# mic-preamp.net
KiCad netlist of a schematic drawn in EAGLE
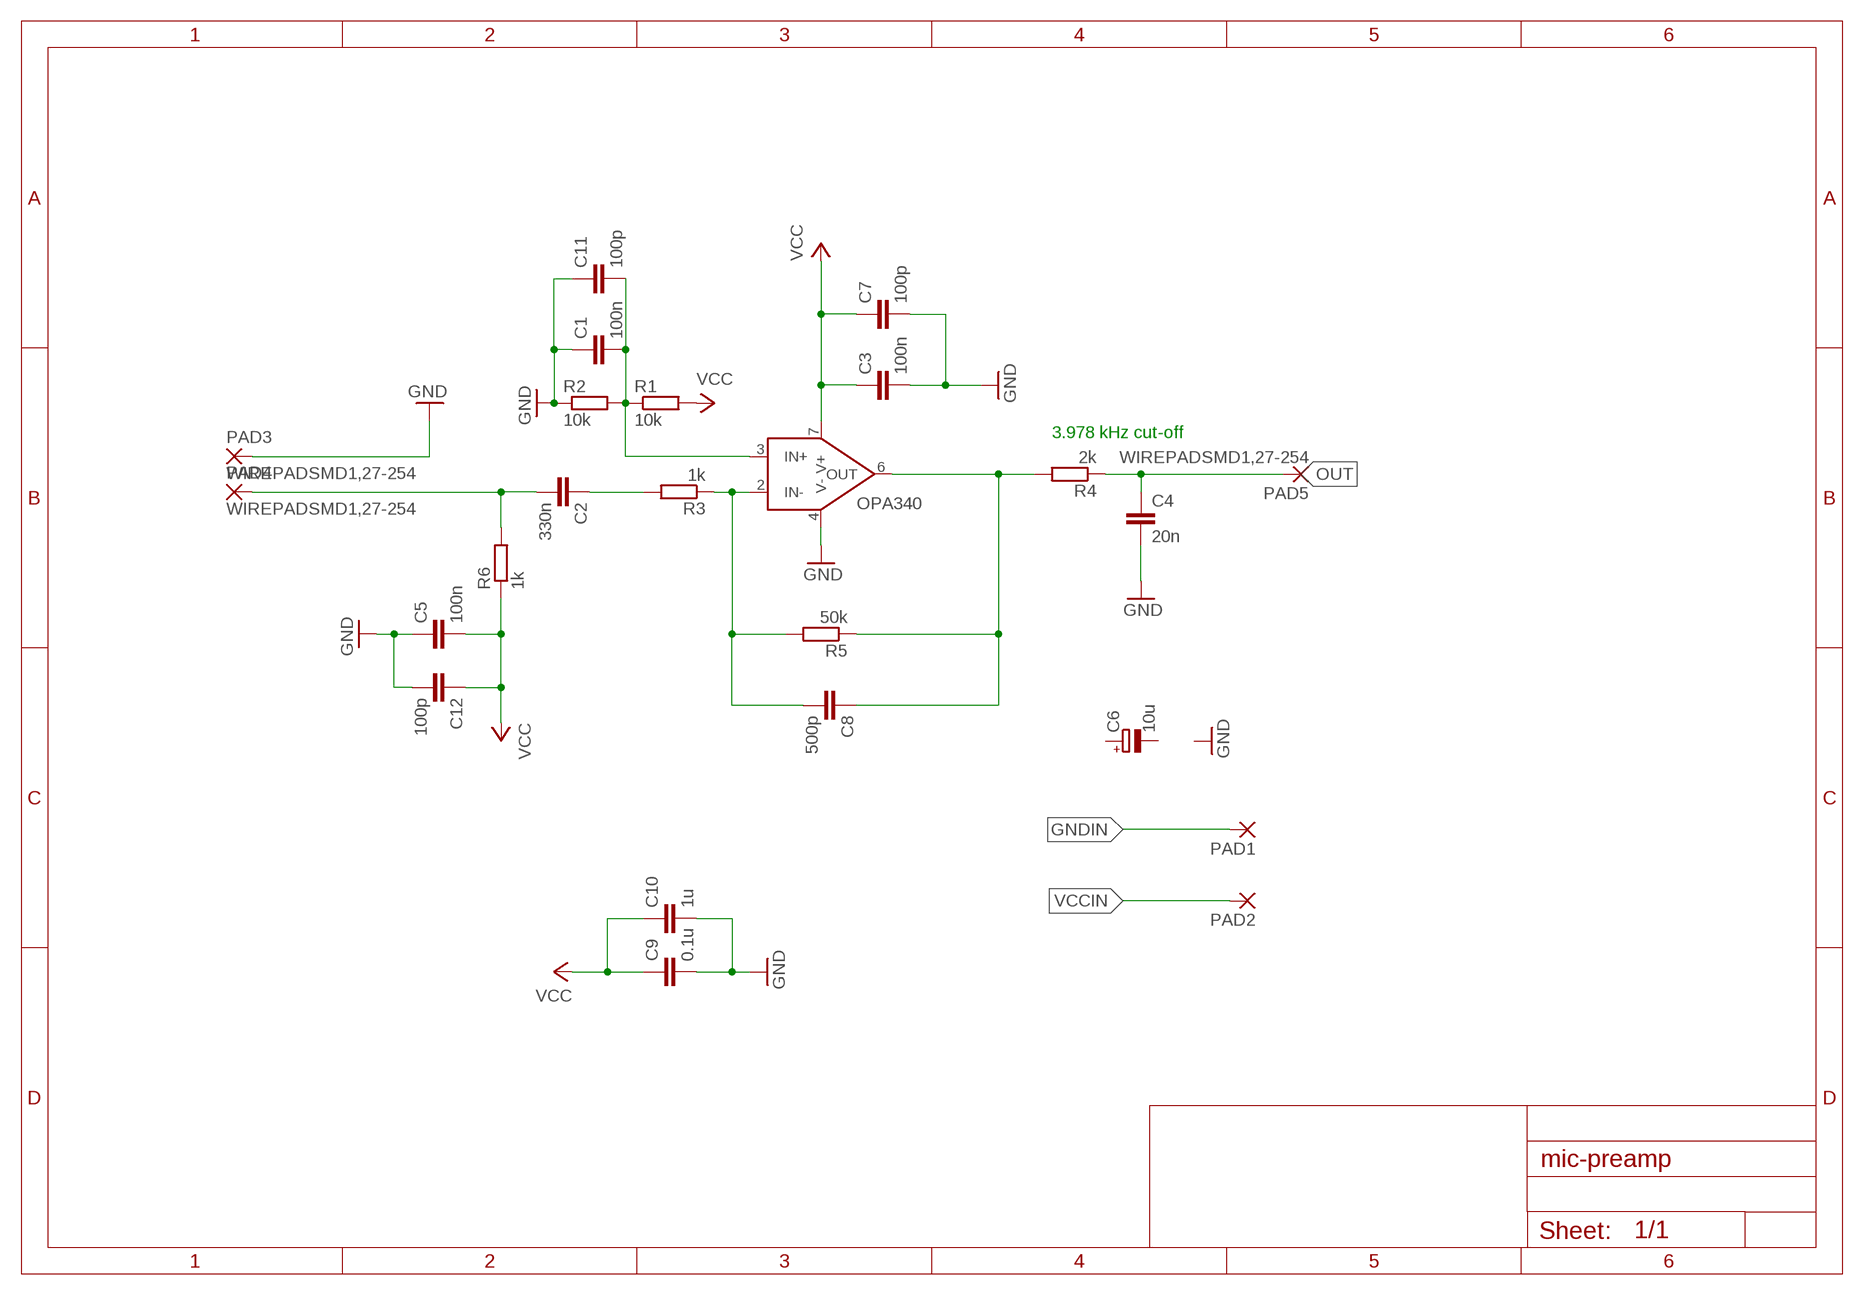
[diagram p0: schematic, sheet 1]

(export (version "E")
  (design (tool "Eeschema 10.0.6"))
  (components
    (comp (ref "C1")
      (value "100n")
      (footprint "eagle-import:C0805")
      (libsource (lib "eagle-import") (part "C-EUC0805"))
    )
    (comp (ref "C2")
      (value "330n")
      (footprint "eagle-import:C0805")
      (libsource (lib "eagle-import") (part "C-EUC0805"))
    )
    (comp (ref "C3")
      (value "100n")
      (footprint "eagle-import:C0805")
      (libsource (lib "eagle-import") (part "C-EUC0805"))
    )
    (comp (ref "C4")
      (value "20n")
      (footprint "eagle-import:C0805")
      (libsource (lib "eagle-import") (part "C-EUC0805"))
    )
    (comp (ref "C5")
      (value "100n")
      (footprint "eagle-import:C0805")
      (libsource (lib "eagle-import") (part "C-EUC0805"))
    )
    (comp (ref "C6")
      (value "10u")
      (footprint "eagle-import:E2,5-6E")
      (libsource (lib "eagle-import") (part "CPOL-EUE2,5-6E"))
    )
    (comp (ref "C7")
      (value "100p")
      (footprint "eagle-import:C0805")
      (libsource (lib "eagle-import") (part "C-EUC0805"))
    )
    (comp (ref "C8")
      (value "500p")
      (footprint "eagle-import:C0805")
      (libsource (lib "eagle-import") (part "C-EUC0805"))
    )
    (comp (ref "C9")
      (value "0.1u")
      (footprint "eagle-import:C0805")
      (libsource (lib "eagle-import") (part "C-EUC0805"))
    )
    (comp (ref "C10")
      (value "1u")
      (footprint "eagle-import:C0805")
      (libsource (lib "eagle-import") (part "C-EUC0805"))
    )
    (comp (ref "C11")
      (value "100p")
      (footprint "eagle-import:C0805")
      (libsource (lib "eagle-import") (part "C-EUC0805"))
    )
    (comp (ref "C12")
      (value "100p")
      (footprint "eagle-import:C0805")
      (libsource (lib "eagle-import") (part "C-EUC0805"))
    )
    (comp (ref "OPA340")
      (value "OPA340")
      (footprint "eagle-import:DIL08")
      (libsource (lib "eagle-import") (part "OPA340"))
    )
    (comp (ref "PAD1")
      (value "WIREPADSMD2,54-5,08")
      (footprint "eagle-import:SMD2,54-5,08")
      (libsource (lib "eagle-import") (part "WIREPADSMD2,54-5,08"))
    )
    (comp (ref "PAD2")
      (value "WIREPADSMD2,54-5,08")
      (footprint "eagle-import:SMD2,54-5,08")
      (libsource (lib "eagle-import") (part "WIREPADSMD2,54-5,08"))
    )
    (comp (ref "PAD3")
      (value "WIREPADSMD1,27-254")
      (footprint "eagle-import:SMD1,27-2,54")
      (libsource (lib "eagle-import") (part "WIREPADSMD1,27-254"))
    )
    (comp (ref "PAD4")
      (value "WIREPADSMD1,27-254")
      (footprint "eagle-import:SMD1,27-2,54")
      (libsource (lib "eagle-import") (part "WIREPADSMD1,27-254"))
    )
    (comp (ref "PAD5")
      (value "WIREPADSMD1,27-254")
      (footprint "eagle-import:SMD1,27-2,54")
      (libsource (lib "eagle-import") (part "WIREPADSMD1,27-254"))
    )
    (comp (ref "R1")
      (value "10k")
      (footprint "eagle-import:R0805")
      (libsource (lib "eagle-import") (part "R-EU_R0805"))
    )
    (comp (ref "R2")
      (value "10k")
      (footprint "eagle-import:R0805")
      (libsource (lib "eagle-import") (part "R-EU_R0805"))
    )
    (comp (ref "R3")
      (value "1k")
      (footprint "eagle-import:R0805")
      (libsource (lib "eagle-import") (part "R-EU_R0805"))
    )
    (comp (ref "R4")
      (value "2k")
      (footprint "eagle-import:R0805")
      (libsource (lib "eagle-import") (part "R-EU_R0805"))
    )
    (comp (ref "R5")
      (value "50k")
      (footprint "eagle-import:R0805")
      (libsource (lib "eagle-import") (part "R-EU_R0805"))
    )
    (comp (ref "R6")
      (value "1k")
      (footprint "eagle-import:R0805")
      (libsource (lib "eagle-import") (part "R-EU_R0805"))
    )
  )
  (nets
    (net (code "1") (name "GND") (class "Default")
      (node (ref "C1") (pin "1") (pinfunction "1_1") (pintype "passive"))
      (node (ref "C10") (pin "2") (pinfunction "2_2") (pintype "passive"))
      (node (ref "C11") (pin "1") (pinfunction "1_1") (pintype "passive"))
      (node (ref "C12") (pin "2") (pinfunction "2_2") (pintype "passive"))
      (node (ref "C3") (pin "2") (pinfunction "2_2") (pintype "passive"))
      (node (ref "C4") (pin "2") (pinfunction "2_2") (pintype "passive"))
      (node (ref "C5") (pin "1") (pinfunction "1_1") (pintype "passive"))
      (node (ref "C7") (pin "2") (pinfunction "2_2") (pintype "passive"))
      (node (ref "C9") (pin "2") (pinfunction "2_2") (pintype "passive"))
      (node (ref "OPA340") (pin "4") (pinfunction "V-_4") (pintype "bidirectional"))
      (node (ref "PAD3") (pin "1") (pinfunction "P_1") (pintype "passive"))
      (node (ref "R2") (pin "1") (pinfunction "1_1") (pintype "passive"))
    )
    (net (code "2") (name "GNDIN") (class "Default")
      (node (ref "PAD1") (pin "1") (pinfunction "P_1") (pintype "passive"))
    )
    (net (code "3") (name "Net-(C2-Pad1)") (class "Default")
      (node (ref "C2") (pin "1") (pinfunction "1_1") (pintype "passive"))
      (node (ref "R3") (pin "2") (pinfunction "2_2") (pintype "passive"))
    )
    (net (code "4") (name "Net-(OPA340-IN+)") (class "Default")
      (node (ref "C1") (pin "2") (pinfunction "2_2") (pintype "passive"))
      (node (ref "C11") (pin "2") (pinfunction "2_2") (pintype "passive"))
      (node (ref "OPA340") (pin "3") (pinfunction "IN+_3") (pintype "bidirectional"))
      (node (ref "R1") (pin "1") (pinfunction "1_1") (pintype "passive"))
      (node (ref "R2") (pin "2") (pinfunction "2_2") (pintype "passive"))
    )
    (net (code "5") (name "Net-(OPA340-IN-)") (class "Default")
      (node (ref "C8") (pin "2") (pinfunction "2_2") (pintype "passive"))
      (node (ref "OPA340") (pin "2") (pinfunction "IN-_2") (pintype "bidirectional"))
      (node (ref "R3") (pin "1") (pinfunction "1_1") (pintype "passive"))
      (node (ref "R5") (pin "2") (pinfunction "2_2") (pintype "passive"))
    )
    (net (code "6") (name "Net-(OPA340-OUT)") (class "Default")
      (node (ref "C8") (pin "1") (pinfunction "1_1") (pintype "passive"))
      (node (ref "OPA340") (pin "6") (pinfunction "OUT_6") (pintype "bidirectional"))
      (node (ref "R4") (pin "2") (pinfunction "2_2") (pintype "passive"))
      (node (ref "R5") (pin "1") (pinfunction "1_1") (pintype "passive"))
    )
    (net (code "7") (name "Net-(PAD4-P)") (class "Default")
      (node (ref "C2") (pin "2") (pinfunction "2_2") (pintype "passive"))
      (node (ref "PAD4") (pin "1") (pinfunction "P_1") (pintype "passive"))
      (node (ref "R6") (pin "2") (pinfunction "2_2") (pintype "passive"))
    )
    (net (code "8") (name "OUT") (class "Default")
      (node (ref "C4") (pin "1") (pinfunction "1_1") (pintype "passive"))
      (node (ref "PAD5") (pin "1") (pinfunction "P_1") (pintype "passive"))
      (node (ref "R4") (pin "1") (pinfunction "1_1") (pintype "passive"))
    )
    (net (code "9") (name "VCC") (class "Default")
      (node (ref "C10") (pin "1") (pinfunction "1_1") (pintype "passive"))
      (node (ref "C12") (pin "1") (pinfunction "1_1") (pintype "passive"))
      (node (ref "C3") (pin "1") (pinfunction "1_1") (pintype "passive"))
      (node (ref "C5") (pin "2") (pinfunction "2_2") (pintype "passive"))
      (node (ref "C7") (pin "1") (pinfunction "1_1") (pintype "passive"))
      (node (ref "C9") (pin "1") (pinfunction "1_1") (pintype "passive"))
      (node (ref "OPA340") (pin "7") (pinfunction "V+_7") (pintype "bidirectional"))
      (node (ref "R1") (pin "2") (pinfunction "2_2") (pintype "passive"))
      (node (ref "R6") (pin "1") (pinfunction "1_1") (pintype "passive"))
    )
    (net (code "10") (name "VCCIN") (class "Default")
      (node (ref "PAD2") (pin "1") (pinfunction "P_1") (pintype "passive"))
    )
    (net (code "11") (name "unconnected-(C6-Pad+)") (class "Default")
      (node (ref "C6") (pin "+") (pinfunction "+_+") (pintype "passive"))
    )
    (net (code "12") (name "unconnected-(C6-Pad-)") (class "Default")
      (node (ref "C6") (pin "-") (pinfunction "-_-") (pintype "passive"))
    )
  )
)
